# DCDC.net
KiCad netlist of a schematic drawn in EAGLE
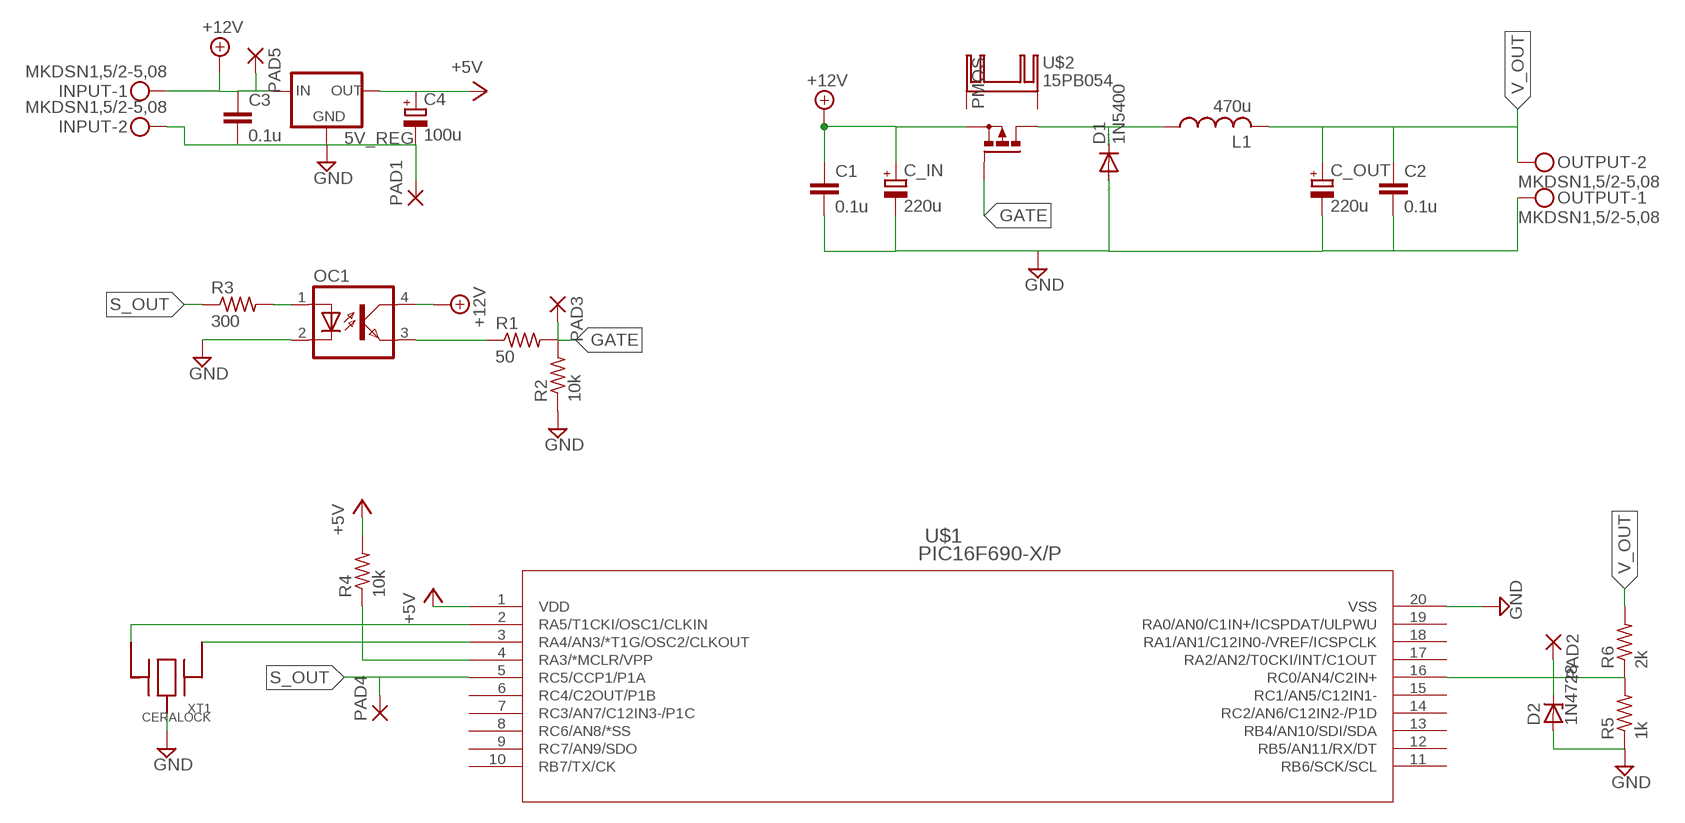
[diagram p0: schematic, sheet 1]

(export (version "E")
  (design (tool "Eeschema 10.0.6"))
  (components
    (comp (ref "5V_REG")
      (value "78XXS")
      (footprint "eagle-import:78XXS")
      (libsource (lib "eagle-import") (part "78XXS"))
    )
    (comp (ref "C1")
      (value "0.1u")
      (footprint "eagle-import:C050-024X044")
      (libsource (lib "eagle-import") (part "C-EU050-024X044"))
    )
    (comp (ref "C2")
      (value "0.1u")
      (footprint "eagle-import:C050-024X044")
      (libsource (lib "eagle-import") (part "C-EU050-024X044"))
    )
    (comp (ref "C3")
      (value "0.1u")
      (footprint "eagle-import:C050-024X044")
      (libsource (lib "eagle-import") (part "C-EU050-024X044"))
    )
    (comp (ref "C4")
      (value "100u")
      (footprint "eagle-import:E2,5-6E")
      (libsource (lib "eagle-import") (part "CPOL-EUE2,5-6E"))
    )
    (comp (ref "C_IN")
      (value "220u")
      (footprint "eagle-import:E3,5-8")
      (libsource (lib "eagle-import") (part "CPOL-EUE3.5-8"))
    )
    (comp (ref "C_OUT")
      (value "220u")
      (footprint "eagle-import:E3,5-8")
      (libsource (lib "eagle-import") (part "CPOL-EUE3.5-8"))
    )
    (comp (ref "D1")
      (value "1N5400")
      (footprint "eagle-import:DO201-15")
      (libsource (lib "eagle-import") (part "1N5400"))
    )
    (comp (ref "D2")
      (value "1N4728")
      (footprint "eagle-import:DO41Z10")
      (libsource (lib "eagle-import") (part "1N4728"))
    )
    (comp (ref "INPUT")
      (value "MKDSN1,5/2-5,08")
      (footprint "eagle-import:MKDSN1,5_2-5,08")
      (libsource (lib "eagle-import") (part "MKDSN1,5/2-5,08"))
    )
    (comp (ref "L1")
      (value "470u")
      (footprint "eagle-import:TCV-471M-9A-8026")
      (libsource (lib "eagle-import") (part "L-US"))
    )
    (comp (ref "OC1")
      (value "PC817")
      (footprint "eagle-import:DIL04")
      (libsource (lib "eagle-import") (part "PC817"))
    )
    (comp (ref "OUTPUT")
      (value "MKDSN1,5/2-5,08")
      (footprint "eagle-import:MKDSN1,5_2-5,08")
      (libsource (lib "eagle-import") (part "MKDSN1,5/2-5,08"))
    )
    (comp (ref "PAD1")
      (value "2,54/0,8")
      (footprint "eagle-import:2,54_0,8")
      (libsource (lib "eagle-import") (part "2,54/0,8"))
    )
    (comp (ref "PAD2")
      (value "2,54/0,8")
      (footprint "eagle-import:2,54_0,8")
      (libsource (lib "eagle-import") (part "2,54/0,8"))
    )
    (comp (ref "PAD3")
      (value "2,54/0,8")
      (footprint "eagle-import:2,54_0,8")
      (libsource (lib "eagle-import") (part "2,54/0,8"))
    )
    (comp (ref "PAD4")
      (value "2,54/0,8")
      (footprint "eagle-import:2,54_0,8")
      (libsource (lib "eagle-import") (part "2,54/0,8"))
    )
    (comp (ref "PAD5")
      (value "2,54/0,8")
      (footprint "eagle-import:2,54_0,8")
      (libsource (lib "eagle-import") (part "2,54/0,8"))
    )
    (comp (ref "PMOS")
      (value "PMOSFET_PTO220BV")
      (footprint "eagle-import:TO220BV")
      (libsource (lib "eagle-import") (part "PMOSFET_PTO220BV"))
    )
    (comp (ref "R1")
      (value "50")
      (footprint "eagle-import:0207_7")
      (libsource (lib "eagle-import") (part "R-US_0207/7"))
    )
    (comp (ref "R2")
      (value "10k")
      (footprint "eagle-import:0207_7")
      (libsource (lib "eagle-import") (part "R-US_0207/7"))
    )
    (comp (ref "R3")
      (value "300")
      (footprint "eagle-import:0207_7")
      (libsource (lib "eagle-import") (part "R-US_0207/7"))
    )
    (comp (ref "R4")
      (value "10k")
      (footprint "eagle-import:0207_7")
      (libsource (lib "eagle-import") (part "R-US_0207/7"))
    )
    (comp (ref "R5")
      (value "1k")
      (footprint "eagle-import:0207_10")
      (libsource (lib "eagle-import") (part "R-US_0207/10"))
    )
    (comp (ref "R6")
      (value "2k")
      (footprint "eagle-import:0207_7")
      (libsource (lib "eagle-import") (part "R-US_0207/7"))
    )
    (comp (ref "U$1")
      (value "PIC16F690-X/P")
      (footprint "eagle-import:PDIP20_300MC")
      (libsource (lib "eagle-import") (part "PIC16F690-X/P"))
    )
    (comp (ref "U$2")
      (value "15PB054")
      (footprint "eagle-import:15PB054")
      (libsource (lib "eagle-import") (part "15PB054"))
    )
    (comp (ref "XT1")
      (value "CERALOCK")
      (footprint "eagle-import:CERALOCK")
      (libsource (lib "eagle-import") (part "CERALOCK"))
    )
  )
  (nets
    (net (code "1") (name "+5V") (class "Default")
      (node (ref "5V_REG") (pin "OUT") (pinfunction "OUT_OUT") (pintype "passive"))
      (node (ref "C4") (pin "+") (pinfunction "+_+") (pintype "passive"))
      (node (ref "R4") (pin "2") (pinfunction "2_2") (pintype "passive"))
      (node (ref "U$1") (pin "1") (pinfunction "VDD_1") (pintype "passive"))
    )
    (net (code "2") (name "+12V") (class "Default")
      (node (ref "5V_REG") (pin "IN") (pinfunction "IN_IN") (pintype "input"))
      (node (ref "C1") (pin "1") (pinfunction "1_1") (pintype "passive"))
      (node (ref "C3") (pin "1") (pinfunction "1_1") (pintype "passive"))
      (node (ref "C_IN") (pin "+") (pinfunction "+_+") (pintype "passive"))
      (node (ref "INPUT") (pin "1") (pinfunction "KL_1") (pintype "passive"))
      (node (ref "OC1") (pin "4") (pinfunction "COL_4") (pintype "passive"))
      (node (ref "PAD5") (pin "1") (pinfunction "P_1") (pintype "passive"))
      (node (ref "PMOS") (pin "S") (pinfunction "S_S") (pintype "passive"))
    )
    (net (code "3") (name "GATE") (class "Default")
      (node (ref "PAD3") (pin "1") (pinfunction "P_1") (pintype "passive"))
      (node (ref "PMOS") (pin "G") (pinfunction "G_G") (pintype "passive"))
      (node (ref "R1") (pin "2") (pinfunction "2_2") (pintype "passive"))
      (node (ref "R2") (pin "2") (pinfunction "2_2") (pintype "passive"))
    )
    (net (code "4") (name "GND") (class "Default")
      (node (ref "5V_REG") (pin "GND") (pinfunction "GND_GND") (pintype "input"))
      (node (ref "C1") (pin "2") (pinfunction "2_2") (pintype "passive"))
      (node (ref "C2") (pin "2") (pinfunction "2_2") (pintype "passive"))
      (node (ref "C3") (pin "2") (pinfunction "2_2") (pintype "passive"))
      (node (ref "C4") (pin "-") (pinfunction "-_-") (pintype "passive"))
      (node (ref "C_IN") (pin "-") (pinfunction "-_-") (pintype "passive"))
      (node (ref "C_OUT") (pin "-") (pinfunction "-_-") (pintype "passive"))
      (node (ref "D1") (pin "A") (pinfunction "A_A") (pintype "passive"))
      (node (ref "D2") (pin "A") (pinfunction "A_A") (pintype "passive"))
      (node (ref "INPUT") (pin "2") (pinfunction "KL_2") (pintype "passive"))
      (node (ref "OC1") (pin "2") (pinfunction "C_2") (pintype "passive"))
      (node (ref "OUTPUT") (pin "1") (pinfunction "KL_1") (pintype "passive"))
      (node (ref "PAD1") (pin "1") (pinfunction "P_1") (pintype "passive"))
      (node (ref "R2") (pin "1") (pinfunction "1_1") (pintype "passive"))
      (node (ref "R5") (pin "1") (pinfunction "1_1") (pintype "passive"))
      (node (ref "U$1") (pin "20") (pinfunction "VSS_20") (pintype "passive"))
      (node (ref "XT1") (pin "P$2") (pinfunction "2_P$2") (pintype "passive"))
    )
    (net (code "5") (name "Net-(L1-1)") (class "Default")
      (node (ref "D1") (pin "C") (pinfunction "C_C") (pintype "passive"))
      (node (ref "L1") (pin "P$1") (pinfunction "1_P$1") (pintype "passive"))
      (node (ref "PMOS") (pin "D") (pinfunction "D_D") (pintype "passive"))
    )
    (net (code "6") (name "Net-(OC1-A)") (class "Default")
      (node (ref "OC1") (pin "1") (pinfunction "A_1") (pintype "passive"))
      (node (ref "R3") (pin "2") (pinfunction "2_2") (pintype "passive"))
    )
    (net (code "7") (name "Net-(OC1-EMIT)") (class "Default")
      (node (ref "OC1") (pin "3") (pinfunction "EMIT_3") (pintype "passive"))
      (node (ref "R1") (pin "1") (pinfunction "1_1") (pintype "passive"))
    )
    (net (code "8") (name "Net-(PAD2-P)") (class "Default")
      (node (ref "D2") (pin "C") (pinfunction "C_C") (pintype "passive"))
      (node (ref "PAD2") (pin "1") (pinfunction "P_1") (pintype "passive"))
      (node (ref "R5") (pin "2") (pinfunction "2_2") (pintype "passive"))
      (node (ref "R6") (pin "1") (pinfunction "1_1") (pintype "passive"))
      (node (ref "U$1") (pin "16") (pinfunction "RC0/AN4/C2IN+_16") (pintype "passive"))
    )
    (net (code "9") (name "Net-(U$1-RA3{slash}*MCLR{slash}VPP)") (class "Default")
      (node (ref "R4") (pin "1") (pinfunction "1_1") (pintype "passive"))
      (node (ref "U$1") (pin "4") (pinfunction "RA3/*MCLR/VPP_4") (pintype "passive"))
    )
    (net (code "10") (name "Net-(U$1-RA4{slash}AN3{slash}*T1G{slash}OSC2{slash}CLKOUT)") (class "Default")
      (node (ref "U$1") (pin "3") (pinfunction "RA4/AN3/*T1G/OSC2/CLKOUT_3") (pintype "passive"))
      (node (ref "XT1") (pin "P$1") (pinfunction "1_P$1") (pintype "passive"))
    )
    (net (code "11") (name "Net-(U$1-RA5{slash}T1CKI{slash}OSC1{slash}CLKIN)") (class "Default")
      (node (ref "U$1") (pin "2") (pinfunction "RA5/T1CKI/OSC1/CLKIN_2") (pintype "passive"))
      (node (ref "XT1") (pin "P$3") (pinfunction "3_P$3") (pintype "passive"))
    )
    (net (code "12") (name "S_OUT") (class "Default")
      (node (ref "PAD4") (pin "1") (pinfunction "P_1") (pintype "passive"))
      (node (ref "R3") (pin "1") (pinfunction "1_1") (pintype "passive"))
      (node (ref "U$1") (pin "5") (pinfunction "RC5/CCP1/P1A_5") (pintype "passive"))
    )
    (net (code "13") (name "V_OUT") (class "Default")
      (node (ref "C2") (pin "1") (pinfunction "1_1") (pintype "passive"))
      (node (ref "C_OUT") (pin "+") (pinfunction "+_+") (pintype "passive"))
      (node (ref "L1") (pin "P$2") (pinfunction "2_P$2") (pintype "passive"))
      (node (ref "OUTPUT") (pin "2") (pinfunction "KL_2") (pintype "passive"))
      (node (ref "R6") (pin "2") (pinfunction "2_2") (pintype "passive"))
    )
    (net (code "14") (name "unconnected-(U$1-RA0{slash}AN0{slash}C1IN+{slash}ICSPDAT{slash}ULPWU-Pad19)") (class "Default")
      (node (ref "U$1") (pin "19") (pinfunction "RA0/AN0/C1IN+/ICSPDAT/ULPWU_19") (pintype "passive"))
    )
    (net (code "15") (name "unconnected-(U$1-RA1{slash}AN1{slash}C12IN0-{slash}VREF{slash}ICSPCLK-Pad18)") (class "Default")
      (node (ref "U$1") (pin "18") (pinfunction "RA1/AN1/C12IN0-/VREF/ICSPCLK_18") (pintype "passive"))
    )
    (net (code "16") (name "unconnected-(U$1-RA2{slash}AN2{slash}T0CKI{slash}INT{slash}C1OUT-Pad17)") (class "Default")
      (node (ref "U$1") (pin "17") (pinfunction "RA2/AN2/T0CKI/INT/C1OUT_17") (pintype "passive"))
    )
    (net (code "17") (name "unconnected-(U$1-RB4{slash}AN10{slash}SDI{slash}SDA-Pad13)") (class "Default")
      (node (ref "U$1") (pin "13") (pinfunction "RB4/AN10/SDI/SDA_13") (pintype "passive"))
    )
    (net (code "18") (name "unconnected-(U$1-RB5{slash}AN11{slash}RX{slash}DT-Pad12)") (class "Default")
      (node (ref "U$1") (pin "12") (pinfunction "RB5/AN11/RX/DT_12") (pintype "passive"))
    )
    (net (code "19") (name "unconnected-(U$1-RB6{slash}SCK{slash}SCL-Pad11)") (class "Default")
      (node (ref "U$1") (pin "11") (pinfunction "RB6/SCK/SCL_11") (pintype "passive"))
    )
    (net (code "20") (name "unconnected-(U$1-RB7{slash}TX{slash}CK-Pad10)") (class "Default")
      (node (ref "U$1") (pin "10") (pinfunction "RB7/TX/CK_10") (pintype "passive"))
    )
    (net (code "21") (name "unconnected-(U$1-RC1{slash}AN5{slash}C12IN1--Pad15)") (class "Default")
      (node (ref "U$1") (pin "15") (pinfunction "RC1/AN5/C12IN1-_15") (pintype "passive"))
    )
    (net (code "22") (name "unconnected-(U$1-RC2{slash}AN6{slash}C12IN2-{slash}P1D-Pad14)") (class "Default")
      (node (ref "U$1") (pin "14") (pinfunction "RC2/AN6/C12IN2-/P1D_14") (pintype "passive"))
    )
    (net (code "23") (name "unconnected-(U$1-RC3{slash}AN7{slash}C12IN3-{slash}P1C-Pad7)") (class "Default")
      (node (ref "U$1") (pin "7") (pinfunction "RC3/AN7/C12IN3-/P1C_7") (pintype "passive"))
    )
    (net (code "24") (name "unconnected-(U$1-RC4{slash}C2OUT{slash}P1B-Pad6)") (class "Default")
      (node (ref "U$1") (pin "6") (pinfunction "RC4/C2OUT/P1B_6") (pintype "passive"))
    )
    (net (code "25") (name "unconnected-(U$1-RC6{slash}AN8{slash}*SS-Pad8)") (class "Default")
      (node (ref "U$1") (pin "8") (pinfunction "RC6/AN8/*SS_8") (pintype "passive"))
    )
    (net (code "26") (name "unconnected-(U$1-RC7{slash}AN9{slash}SDO-Pad9)") (class "Default")
      (node (ref "U$1") (pin "9") (pinfunction "RC7/AN9/SDO_9") (pintype "passive"))
    )
    (net (code "27") (name "unconnected-(U$2-K-PadP$1)") (class "Default")
      (node (ref "U$2") (pin "P$1") (pinfunction "K_P$1") (pintype "passive"))
    )
    (net (code "28") (name "unconnected-(U$2-K-PadP$2)") (class "Default")
      (node (ref "U$2") (pin "P$2") (pinfunction "K_P$2") (pintype "passive"))
    )
  )
)
